# Tiny817_Xplained_Pro_current_measurement.net
KiCad netlist of a schematic drawn in Altium Designer
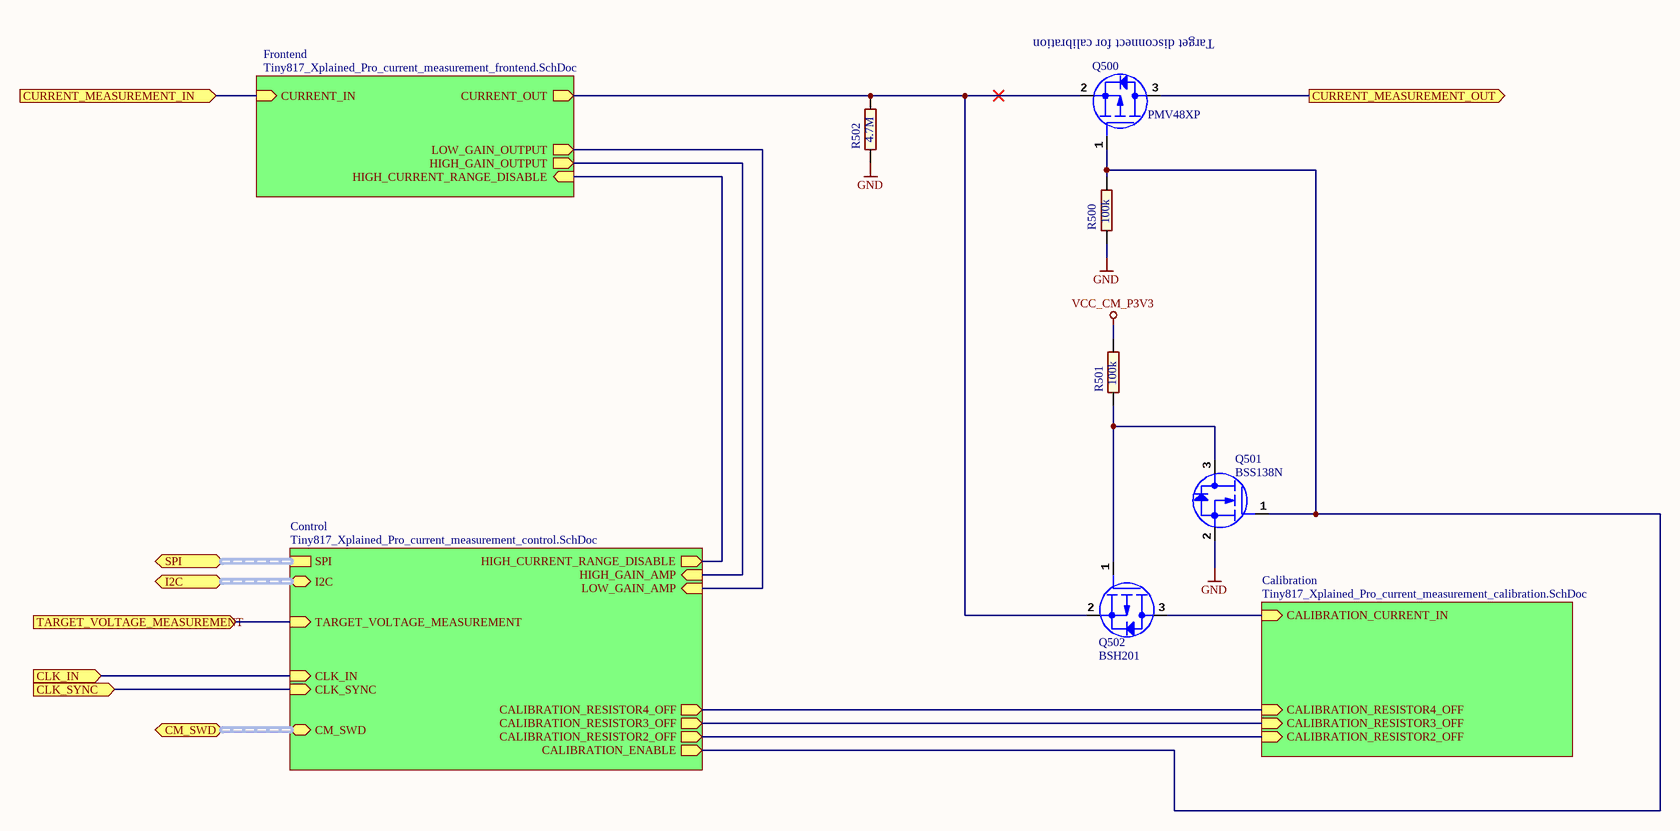
[diagram p0: Tiny817_Xplained_Pro_current_measurement.SchDoc]

(export (version "E")
  (design (tool "Eeschema 10.0.6"))
  (components
    (comp (ref "Q500")
      (value "PMV48XP")
      (footprint "AP5-00002")
      (fields (field (name "MANUFACTURER") "NXP") (field (name "MPN") "PMV48XP,215"))
      (libsource (lib "AltiumDbLib") (part "MOSFET_P_GSD"))
    )
    (comp (ref "Q501")
      (value "BSS138N")
      (footprint "AP5-00002")
      (fields (field (name "MANUFACTURER") "Infineon"))
      (libsource (lib "AltiumDbLib") (part "MOSFET_N_GSD"))
    )
    (comp (ref "Q502")
      (value "BSH201")
      (footprint "AP5-00002")
      (fields (field (name "MANUFACTURER") "NXP") (field (name "MPN") "BSH201,215"))
      (libsource (lib "AltiumDbLib") (part "MOSFET_P_GSD"))
    )
    (comp (ref "R500")
      (value "100k")
      (footprint "AP2-00011")
      (description "Thick film resistor, SMD 0402, 1/16W, 1%")
      (fields (field (name "TOLERANCE") "1 %") (field (name "MANUFACTURER") "ASJ"))
      (libsource (lib "") (part "R2_1"))
    )
    (comp (ref "R501")
      (value "100k")
      (footprint "AP2-00011")
      (description "Thick film resistor, SMD 0402, 1/16W, 1%")
      (fields (field (name "TOLERANCE") "1 %") (field (name "MANUFACTURER") "ASJ"))
      (libsource (lib "AltiumDbLib") (part "R2"))
    )
    (comp (ref "R502")
      (value "4.7M")
      (footprint "AP2-00011")
      (description "Thick film SMD 0402 1/16W 1%")
      (fields (field (name "TOLERANCE") "1 %") (field (name "MANUFACTURER") "YAGEO CORP"))
      (libsource (lib "") (part "R2_1"))
    )
  )
  (nets
    (net (code "4") (name "/CALIBRATION_CURRENT_IN") (class "Default")
      (node (ref "Q502") (pin "3") (pinfunction "D_3") (pintype "passive"))
    )
    (net (code "5") (name "/CALIBRATION_ENABLE") (class "Default")
      (node (ref "Q500") (pin "1") (pinfunction "G_1") (pintype "passive"))
      (node (ref "Q501") (pin "1") (pinfunction "G_1") (pintype "passive"))
      (node (ref "R500") (pin "2") (pinfunction "2_2") (pintype "passive"))
    )
    (net (code "13") (name "/CURRENT_MEASUREMENT_OUT") (class "Default")
      (node (ref "Q500") (pin "3") (pinfunction "D_3") (pintype "passive"))
    )
    (net (code "14") (name "/CURRENT_OUT") (class "Default")
      (node (ref "Q500") (pin "2") (pinfunction "S_2") (pintype "passive"))
      (node (ref "Q502") (pin "2") (pinfunction "S_2") (pintype "passive"))
      (node (ref "R502") (pin "2") (pinfunction "2_2") (pintype "passive"))
    )
    (net (code "21") (name "GND") (class "Default")
      (node (ref "Q501") (pin "2") (pinfunction "S_2") (pintype "passive"))
      (node (ref "R500") (pin "1") (pinfunction "1_1") (pintype "passive"))
      (node (ref "R502") (pin "1") (pinfunction "1_1") (pintype "passive"))
    )
    (net (code "22") (name "Net-(Q501-D)") (class "Default")
      (node (ref "Q501") (pin "3") (pinfunction "D_3") (pintype "passive"))
      (node (ref "Q502") (pin "1") (pinfunction "G_1") (pintype "passive"))
      (node (ref "R501") (pin "1") (pinfunction "1_1") (pintype "passive"))
    )
    (net (code "23") (name "VCC_CM_P3V3") (class "Default")
      (node (ref "R501") (pin "2") (pinfunction "2_2") (pintype "passive"))
    )
  )
)
